# 464421_22-01_RF_OUT.net
KiCad netlist of a schematic drawn in Altium Designer
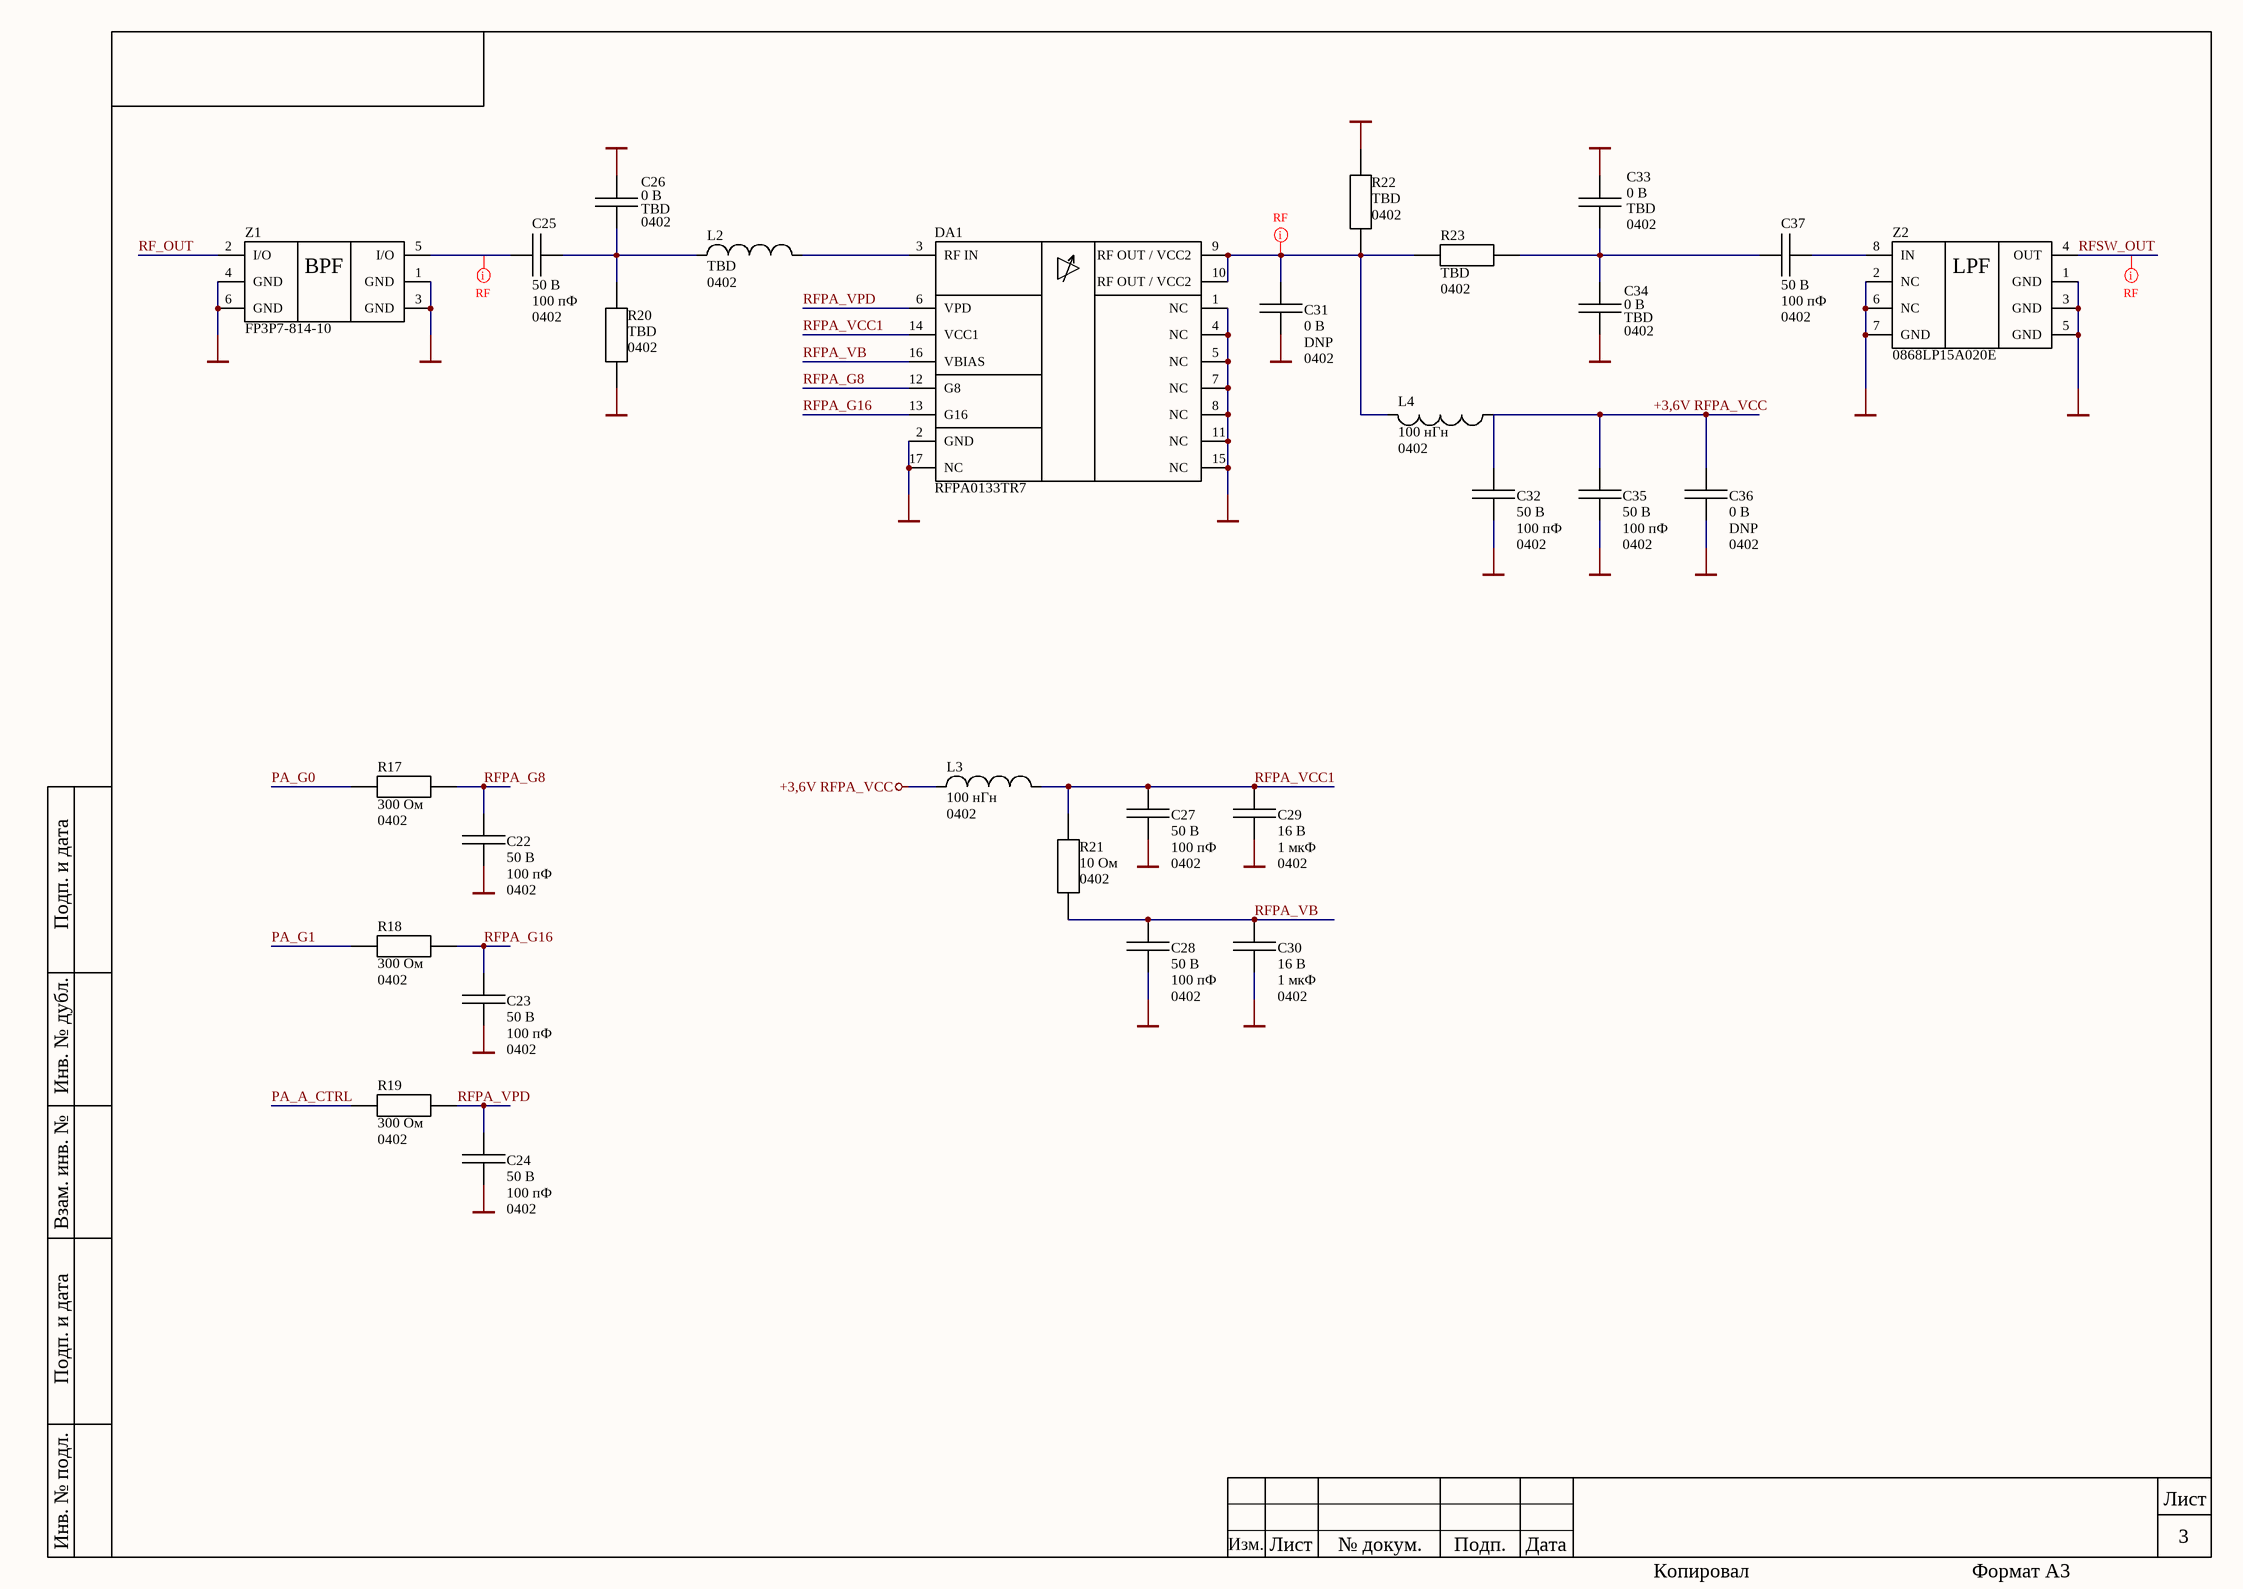
[diagram p0: МПСУ.464421.22-01 RF_OUT.SchDoc]

(export (version "E")
  (design (tool "Eeschema 10.0.6"))
  (components
    (comp (ref "C22")
      (value "100 пФ")
      (footprint "Passive_V2_0:CAPC100X50X55L20N")
      (description "Capacitor 0402")
      (fields
        (field (name "PARTNUMBER") "GRM1555C1H101JZ01D")
        (field (name "MANUFACTURER") "Murata")
        (field (name "PEAK_CONDITION") "50 В")
        (field (name "PACKAGE") "0402")
        (field (name "DESIGNER") "Свидерский")
      )
      (libsource (lib "Passive_V2_0") (part "C 0402"))
    )
    (comp (ref "C23")
      (value "100 пФ")
      (footprint "Passive_V2_0:CAPC100X50X55L20N")
      (description "Capacitor 0402")
      (fields
        (field (name "PARTNUMBER") "GRM1555C1H101JZ01D")
        (field (name "MANUFACTURER") "Murata")
        (field (name "PEAK_CONDITION") "50 В")
        (field (name "PACKAGE") "0402")
        (field (name "DESIGNER") "Свидерский")
      )
      (libsource (lib "Passive_V2_0") (part "C 0402"))
    )
    (comp (ref "C24")
      (value "100 пФ")
      (footprint "Passive_V2_0:CAPC100X50X55L20N")
      (description "Capacitor 0402")
      (fields
        (field (name "PARTNUMBER") "GRM1555C1H101JZ01D")
        (field (name "MANUFACTURER") "Murata")
        (field (name "PEAK_CONDITION") "50 В")
        (field (name "PACKAGE") "0402")
        (field (name "DESIGNER") "Свидерский")
      )
      (libsource (lib "Passive_V2_0") (part "C 0402"))
    )
    (comp (ref "C25")
      (value "100 пФ")
      (footprint "Passive_V2_0:CAPC100X50X55L20N")
      (description "Capacitor 0402")
      (fields
        (field (name "PARTNUMBER") "GRM1555C1H101JZ01D")
        (field (name "MANUFACTURER") "Murata")
        (field (name "PEAK_CONDITION") "50 В")
        (field (name "PACKAGE") "0402")
        (field (name "DESIGNER") "Свидерский")
      )
      (libsource (lib "Passive_V2_0") (part "C 0402"))
    )
    (comp (ref "C26")
      (value "TBD")
      (footprint "Passive_V2_0:CAPC100X50X55L20N")
      (description "Capacitor 0402")
      (fields
        (field (name "TOLERANCE") "0 %")
        (field (name "PEAK_CONDITION") "0 В")
        (field (name "PACKAGE") "0402")
        (field (name "Comment") "TBD 0402")
        (field (name "DESIGNER") "Свидерский")
      )
      (libsource (lib "Passive_V2_0") (part "C 0402"))
    )
    (comp (ref "C27")
      (value "100 пФ")
      (footprint "Passive_V2_0:CAPC100X50X55L20N")
      (description "Capacitor 0402")
      (fields
        (field (name "PARTNUMBER") "GRM1555C1H101JZ01D")
        (field (name "MANUFACTURER") "Murata")
        (field (name "PEAK_CONDITION") "50 В")
        (field (name "PACKAGE") "0402")
        (field (name "DESIGNER") "Свидерский")
      )
      (libsource (lib "Passive_V2_0") (part "C 0402"))
    )
    (comp (ref "C28")
      (value "100 пФ")
      (footprint "Passive_V2_0:CAPC100X50X55L20N")
      (description "Capacitor 0402")
      (fields
        (field (name "PARTNUMBER") "GRM1555C1H101JZ01D")
        (field (name "MANUFACTURER") "Murata")
        (field (name "PEAK_CONDITION") "50 В")
        (field (name "PACKAGE") "0402")
        (field (name "DESIGNER") "Свидерский")
      )
      (libsource (lib "Passive_V2_0") (part "C 0402"))
    )
    (comp (ref "C29")
      (value "1 мкФ")
      (footprint "Passive_V2_0:CAPC100X50X55L20N")
      (description "Capacitor 0402")
      (fields
        (field (name "PARTNUMBER") "GRM155R61C105KA12D")
        (field (name "MANUFACTURER") "Murata")
        (field (name "PEAK_CONDITION") "16 В")
        (field (name "PACKAGE") "0402")
        (field (name "DESIGNER") "Свидерский")
      )
      (libsource (lib "Passive_V2_0") (part "C 0402"))
    )
    (comp (ref "C30")
      (value "1 мкФ")
      (footprint "Passive_V2_0:CAPC100X50X55L20N")
      (description "Capacitor 0402")
      (fields
        (field (name "PARTNUMBER") "GRM155R61C105KA12D")
        (field (name "MANUFACTURER") "Murata")
        (field (name "PEAK_CONDITION") "16 В")
        (field (name "PACKAGE") "0402")
        (field (name "DESIGNER") "Свидерский")
      )
      (libsource (lib "Passive_V2_0") (part "C 0402"))
    )
    (comp (ref "C31")
      (value "DNP")
      (footprint "Passive_V2_0:CAPC100X50X55L20N")
      (description "Capacitor 0402")
      (fields
        (field (name "TOLERANCE") "0 %")
        (field (name "PEAK_CONDITION") "0 В")
        (field (name "PACKAGE") "0402")
        (field (name "Comment") "DNP 0402")
        (field (name "DESIGNER") "Свидерский")
      )
      (libsource (lib "Passive_V2_0") (part "C 0402"))
    )
    (comp (ref "C32")
      (value "100 пФ")
      (footprint "Passive_V2_0:CAPC100X50X55L20N")
      (description "Capacitor 0402")
      (fields
        (field (name "PARTNUMBER") "GRM1555C1H101JZ01D")
        (field (name "MANUFACTURER") "Murata")
        (field (name "PEAK_CONDITION") "50 В")
        (field (name "PACKAGE") "0402")
        (field (name "DESIGNER") "Свидерский")
      )
      (libsource (lib "Passive_V2_0") (part "C 0402"))
    )
    (comp (ref "C33")
      (value "TBD")
      (footprint "Passive_V2_0:CAPC100X50X55L20N")
      (description "Capacitor 0402")
      (fields
        (field (name "TOLERANCE") "0 %")
        (field (name "PEAK_CONDITION") "0 В")
        (field (name "PACKAGE") "0402")
        (field (name "Comment") "TBD 0402")
        (field (name "DESIGNER") "Свидерский")
      )
      (libsource (lib "Passive_V2_0") (part "C 0402"))
    )
    (comp (ref "C34")
      (value "TBD")
      (footprint "Passive_V2_0:CAPC100X50X55L20N")
      (description "Capacitor 0402")
      (fields
        (field (name "TOLERANCE") "0 %")
        (field (name "PEAK_CONDITION") "0 В")
        (field (name "PACKAGE") "0402")
        (field (name "Comment") "TBD 0402")
        (field (name "DESIGNER") "Свидерский")
      )
      (libsource (lib "Passive_V2_0") (part "C 0402"))
    )
    (comp (ref "C35")
      (value "100 пФ")
      (footprint "Passive_V2_0:CAPC100X50X55L20N")
      (description "Capacitor 0402")
      (fields
        (field (name "PARTNUMBER") "GRM1555C1H101JZ01D")
        (field (name "MANUFACTURER") "Murata")
        (field (name "PEAK_CONDITION") "50 В")
        (field (name "PACKAGE") "0402")
        (field (name "DESIGNER") "Свидерский")
      )
      (libsource (lib "Passive_V2_0") (part "C 0402"))
    )
    (comp (ref "C36")
      (value "DNP")
      (footprint "Passive_V2_0:CAPC100X50X55L20N")
      (description "Capacitor 0402")
      (fields
        (field (name "TOLERANCE") "0 %")
        (field (name "PEAK_CONDITION") "0 В")
        (field (name "PACKAGE") "0402")
        (field (name "Comment") "DNP 0402")
        (field (name "DESIGNER") "Свидерский")
      )
      (libsource (lib "Passive_V2_0") (part "C 0402"))
    )
    (comp (ref "C37")
      (value "100 пФ")
      (footprint "Passive_V2_0:CAPC100X50X55L20N")
      (description "Capacitor 0402")
      (fields
        (field (name "PARTNUMBER") "GRM1555C1H101JZ01D")
        (field (name "MANUFACTURER") "Murata")
        (field (name "PEAK_CONDITION") "50 В")
        (field (name "PACKAGE") "0402")
        (field (name "DESIGNER") "Свидерский")
      )
      (libsource (lib "Passive_V2_0") (part "C 0402"))
    )
    (comp (ref "DA1")
      (value "RFPA0133TR7")
      (footprint "IC_V2_0:QFN50P300X300X90_HS-17N")
      (description "380 to 960 MHz, 3 to 5V programmable gain high efficiency power amplifier")
      (fields
        (field (name "MANUFACTURER") "RFD, Qorvo")
        (field (name "PARTNUMBER") "RFPA0133TR7")
        (field (name "DESIGNER") "Лазба")
      )
      (libsource (lib "IC_V2_0") (part "RFPA0133TR7"))
    )
    (comp (ref "L2")
      (value "TBD")
      (footprint "Passive_V2_0:INDC100X50X60L10N")
      (description "Inductor 0402")
      (fields
        (field (name "TOLERANCE") "0 %")
        (field (name "PACKAGE") "0402")
        (field (name "Comment") "TBD 0402")
        (field (name "DESIGNER") "Свидерский")
      )
      (libsource (lib "Passive_V2_0") (part "L 0402"))
    )
    (comp (ref "L3")
      (value "100 нГн")
      (footprint "Passive_V2_0:INDC100X50X60L10N")
      (description "Inductor 0402")
      (fields
        (field (name "PARTNUMBER") "LQG15HNR10J02D")
        (field (name "TOLERANCE") "5 %")
        (field (name "PACKAGE") "0402")
        (field (name "DESIGNER") "Свидерский")
      )
      (libsource (lib "Passive_V2_0") (part "L 0402"))
    )
    (comp (ref "L4")
      (value "100 нГн")
      (footprint "Passive_V2_0:INDC100X50X60L10N")
      (description "Inductor 0402")
      (fields
        (field (name "PARTNUMBER") "LQG15HNR10J02D")
        (field (name "TOLERANCE") "5 %")
        (field (name "PACKAGE") "0402")
        (field (name "DESIGNER") "Свидерский")
      )
      (libsource (lib "Passive_V2_0") (part "L 0402"))
    )
    (comp (ref "R17")
      (value "300 Ом")
      (footprint "Passive_V2_0:RESC100X50X40L25N")
      (description "Resistor 0402")
      (fields
        (field (name "PARTNUMBER") "RI0402L301JT")
        (field (name "TOLERANCE") "5 %")
        (field (name "PACKAGE") "0402")
        (field (name "DESIGNER") "Свидерский")
      )
      (libsource (lib "Passive_V2_0") (part "R 0402"))
    )
    (comp (ref "R18")
      (value "300 Ом")
      (footprint "Passive_V2_0:RESC100X50X40L25N")
      (description "Resistor 0402")
      (fields
        (field (name "PARTNUMBER") "RI0402L301JT")
        (field (name "TOLERANCE") "5 %")
        (field (name "PACKAGE") "0402")
        (field (name "DESIGNER") "Свидерский")
      )
      (libsource (lib "Passive_V2_0") (part "R 0402"))
    )
    (comp (ref "R19")
      (value "300 Ом")
      (footprint "Passive_V2_0:RESC100X50X40L25N")
      (description "Resistor 0402")
      (fields
        (field (name "PARTNUMBER") "RI0402L301JT")
        (field (name "TOLERANCE") "5 %")
        (field (name "PACKAGE") "0402")
        (field (name "DESIGNER") "Свидерский")
      )
      (libsource (lib "Passive_V2_0") (part "R 0402"))
    )
    (comp (ref "R20")
      (value "TBD")
      (footprint "Passive_V2_0:RESC100X50X40L25N")
      (description "Resistor 0402")
      (fields
        (field (name "TOLERANCE") "0 %")
        (field (name "PACKAGE") "0402")
        (field (name "Comment") "TBD 0402")
        (field (name "DESIGNER") "Свидерский")
      )
      (libsource (lib "") (part "R 0402_1"))
    )
    (comp (ref "R21")
      (value "10 Ом")
      (footprint "Passive_V2_0:RESC100X50X40L25N")
      (description "Resistor 0402")
      (fields
        (field (name "PARTNUMBER") "RI0402L100JT")
        (field (name "TOLERANCE") "5 %")
        (field (name "PACKAGE") "0402")
        (field (name "DESIGNER") "Свидерский")
      )
      (libsource (lib "") (part "R 0402_1"))
    )
    (comp (ref "R22")
      (value "TBD")
      (footprint "Passive_V2_0:RESC100X50X40L25N")
      (description "Resistor 0402")
      (fields
        (field (name "TOLERANCE") "0 %")
        (field (name "PACKAGE") "0402")
        (field (name "Comment") "TBD 0402")
        (field (name "DESIGNER") "Свидерский")
      )
      (libsource (lib "") (part "R 0402_2"))
    )
    (comp (ref "R23")
      (value "TBD")
      (footprint "Passive_V2_0:RESC100X50X40L25N")
      (description "Resistor 0402")
      (fields
        (field (name "TOLERANCE") "0 %")
        (field (name "PACKAGE") "0402")
        (field (name "Comment") "TBD 0402")
        (field (name "DESIGNER") "Свидерский")
      )
      (libsource (lib "Passive_V2_0") (part "R 0402"))
    )
    (comp (ref "Z1")
      (value "FP3P7-814-10")
      (footprint "Passive_V2_0:LCCS110P300X300X146-6N")
      (description "BandPass Filter")
      (fields
        (field (name "MANUFACTURER") "БУТИС")
        (field (name "PARTNUMBER") "FP3P7-814-10")
        (field (name "DESIGNER") "Лазба")
      )
      (libsource (lib "Passive_V2_0") (part "FP3P7-***-**"))
    )
    (comp (ref "Z2")
      (value "0868LP15A020E")
      (footprint "Passive_V2_0:LCC065P125X200X085-8")
      (fields
        (field (name "MANUFACTURER") "Johanson Technology Inc.")
        (field (name "PARTNUMBER") "0868LP15A020E")
        (field (name "DESIGNER") "Лазба")
      )
      (libsource (lib "Passive_V2_0") (part "0868LP15A020"))
    )
  )
  (nets
    (net (code "1") (name "+3,6V RFPA_VCC") (class "Default")
      (node (ref "C32") (pin "1") (pinfunction "1_1") (pintype "passive"))
      (node (ref "C35") (pin "1") (pinfunction "1_1") (pintype "passive"))
      (node (ref "C36") (pin "1") (pinfunction "1_1") (pintype "passive"))
      (node (ref "L3") (pin "1") (pinfunction "1_1") (pintype "passive"))
      (node (ref "L4") (pin "1") (pinfunction "1_1") (pintype "passive"))
    )
    (net (code "2") (name "/PA_A_CTRL") (class "Default")
      (node (ref "R19") (pin "1") (pinfunction "1_1") (pintype "passive"))
    )
    (net (code "3") (name "/PA_G0") (class "Default")
      (node (ref "R17") (pin "1") (pinfunction "1_1") (pintype "passive"))
    )
    (net (code "4") (name "/PA_G1") (class "Default")
      (node (ref "R18") (pin "1") (pinfunction "1_1") (pintype "passive"))
    )
    (net (code "5") (name "/RFPA_G8") (class "Default")
      (node (ref "C22") (pin "2") (pinfunction "2_2") (pintype "passive"))
      (node (ref "DA1") (pin "12") (pinfunction "G8_12") (pintype "passive"))
      (node (ref "R17") (pin "2") (pinfunction "2_2") (pintype "passive"))
    )
    (net (code "6") (name "/RFPA_G16") (class "Default")
      (node (ref "C23") (pin "2") (pinfunction "2_2") (pintype "passive"))
      (node (ref "DA1") (pin "13") (pinfunction "G16_13") (pintype "passive"))
      (node (ref "R18") (pin "2") (pinfunction "2_2") (pintype "passive"))
    )
    (net (code "7") (name "/RFPA_VB") (class "Default")
      (node (ref "C28") (pin "2") (pinfunction "2_2") (pintype "passive"))
      (node (ref "C30") (pin "2") (pinfunction "2_2") (pintype "passive"))
      (node (ref "DA1") (pin "16") (pinfunction "VBIAS_16") (pintype "passive"))
      (node (ref "R21") (pin "2") (pinfunction "2_2") (pintype "passive"))
    )
    (net (code "8") (name "/RFPA_VPD") (class "Default")
      (node (ref "C24") (pin "2") (pinfunction "2_2") (pintype "passive"))
      (node (ref "DA1") (pin "6") (pinfunction "VPD_6") (pintype "passive"))
      (node (ref "R19") (pin "2") (pinfunction "2_2") (pintype "passive"))
    )
    (net (code "9") (name "/RFPA_VСС1") (class "Default")
      (node (ref "C27") (pin "2") (pinfunction "2_2") (pintype "passive"))
      (node (ref "C29") (pin "2") (pinfunction "2_2") (pintype "passive"))
      (node (ref "DA1") (pin "14") (pinfunction "VCC1_14") (pintype "passive"))
      (node (ref "L3") (pin "2") (pinfunction "2_2") (pintype "passive"))
      (node (ref "R21") (pin "1") (pinfunction "1_1") (pintype "passive"))
    )
    (net (code "10") (name "/RFSW_OUT") (class "Default")
      (node (ref "Z2") (pin "4") (pinfunction "OUT_4") (pintype "passive"))
    )
    (net (code "11") (name "/RF_OUT") (class "Default")
      (node (ref "Z1") (pin "2") (pinfunction "I/O_2") (pintype "passive"))
    )
    (net (code "12") (name "GND") (class "Default")
      (node (ref "C22") (pin "1") (pinfunction "1_1") (pintype "passive"))
      (node (ref "C23") (pin "1") (pinfunction "1_1") (pintype "passive"))
      (node (ref "C24") (pin "1") (pinfunction "1_1") (pintype "passive"))
      (node (ref "C26") (pin "2") (pinfunction "2_2") (pintype "passive"))
      (node (ref "C27") (pin "1") (pinfunction "1_1") (pintype "passive"))
      (node (ref "C28") (pin "1") (pinfunction "1_1") (pintype "passive"))
      (node (ref "C29") (pin "1") (pinfunction "1_1") (pintype "passive"))
      (node (ref "C30") (pin "1") (pinfunction "1_1") (pintype "passive"))
      (node (ref "C31") (pin "2") (pinfunction "2_2") (pintype "passive"))
      (node (ref "C32") (pin "2") (pinfunction "2_2") (pintype "passive"))
      (node (ref "C33") (pin "2") (pinfunction "2_2") (pintype "passive"))
      (node (ref "C34") (pin "2") (pinfunction "2_2") (pintype "passive"))
      (node (ref "C35") (pin "2") (pinfunction "2_2") (pintype "passive"))
      (node (ref "C36") (pin "2") (pinfunction "2_2") (pintype "passive"))
      (node (ref "DA1") (pin "1") (pinfunction "NC_1") (pintype "passive"))
      (node (ref "DA1") (pin "11") (pinfunction "NC_11") (pintype "passive"))
      (node (ref "DA1") (pin "15") (pinfunction "NC_15") (pintype "passive"))
      (node (ref "DA1") (pin "17") (pinfunction "NC_17") (pintype "passive"))
      (node (ref "DA1") (pin "2") (pinfunction "GND_2") (pintype "passive"))
      (node (ref "DA1") (pin "4") (pinfunction "NC_4") (pintype "passive"))
      (node (ref "DA1") (pin "5") (pinfunction "NC_5") (pintype "passive"))
      (node (ref "DA1") (pin "7") (pinfunction "NC_7") (pintype "passive"))
      (node (ref "DA1") (pin "8") (pinfunction "NC_8") (pintype "passive"))
      (node (ref "R20") (pin "2") (pinfunction "2_2") (pintype "passive"))
      (node (ref "R22") (pin "2") (pinfunction "2_2") (pintype "passive"))
      (node (ref "Z1") (pin "1") (pinfunction "GND_1") (pintype "passive"))
      (node (ref "Z1") (pin "3") (pinfunction "GND_3") (pintype "passive"))
      (node (ref "Z1") (pin "4") (pinfunction "GND_4") (pintype "passive"))
      (node (ref "Z1") (pin "6") (pinfunction "GND_6") (pintype "passive"))
      (node (ref "Z2") (pin "1") (pinfunction "GND_1") (pintype "passive"))
      (node (ref "Z2") (pin "2") (pinfunction "NC_2") (pintype "passive"))
      (node (ref "Z2") (pin "3") (pinfunction "GND_3") (pintype "passive"))
      (node (ref "Z2") (pin "5") (pinfunction "GND_5") (pintype "passive"))
      (node (ref "Z2") (pin "6") (pinfunction "NC_6") (pintype "passive"))
      (node (ref "Z2") (pin "7") (pinfunction "GND_7") (pintype "passive"))
    )
    (net (code "13") (name "Net-(C25-Pad1)") (class "Default")
      (node (ref "C25") (pin "1") (pinfunction "1_1") (pintype "passive"))
      (node (ref "Z1") (pin "5") (pinfunction "I/O_5") (pintype "passive"))
    )
    (net (code "14") (name "Net-(C25-Pad2)") (class "Default")
      (node (ref "C25") (pin "2") (pinfunction "2_2") (pintype "passive"))
      (node (ref "C26") (pin "1") (pinfunction "1_1") (pintype "passive"))
      (node (ref "L2") (pin "1") (pinfunction "1_1") (pintype "passive"))
      (node (ref "R20") (pin "1") (pinfunction "1_1") (pintype "passive"))
    )
    (net (code "15") (name "Net-(C31-Pad1)") (class "Default")
      (node (ref "C31") (pin "1") (pinfunction "1_1") (pintype "passive"))
      (node (ref "DA1") (pin "10") (pinfunction "RF_OUT_/_VCC2_10") (pintype "passive"))
      (node (ref "DA1") (pin "9") (pinfunction "RF_OUT_/_VCC2_9") (pintype "passive"))
      (node (ref "L4") (pin "2") (pinfunction "2_2") (pintype "passive"))
      (node (ref "R22") (pin "1") (pinfunction "1_1") (pintype "passive"))
      (node (ref "R23") (pin "1") (pinfunction "1_1") (pintype "passive"))
    )
    (net (code "16") (name "Net-(C33-Pad1)") (class "Default")
      (node (ref "C33") (pin "1") (pinfunction "1_1") (pintype "passive"))
      (node (ref "C34") (pin "1") (pinfunction "1_1") (pintype "passive"))
      (node (ref "C37") (pin "1") (pinfunction "1_1") (pintype "passive"))
      (node (ref "R23") (pin "2") (pinfunction "2_2") (pintype "passive"))
    )
    (net (code "17") (name "Net-(DA1-RF_IN)") (class "Default")
      (node (ref "DA1") (pin "3") (pinfunction "RF_IN_3") (pintype "passive"))
      (node (ref "L2") (pin "2") (pinfunction "2_2") (pintype "passive"))
    )
    (net (code "18") (name "Net-(Z2-IN)") (class "Default")
      (node (ref "C37") (pin "2") (pinfunction "2_2") (pintype "passive"))
      (node (ref "Z2") (pin "8") (pinfunction "IN_8") (pintype "passive"))
    )
  )
)
